# Blank_Ext_Board.net
KiCad netlist of a schematic drawn in EAGLE
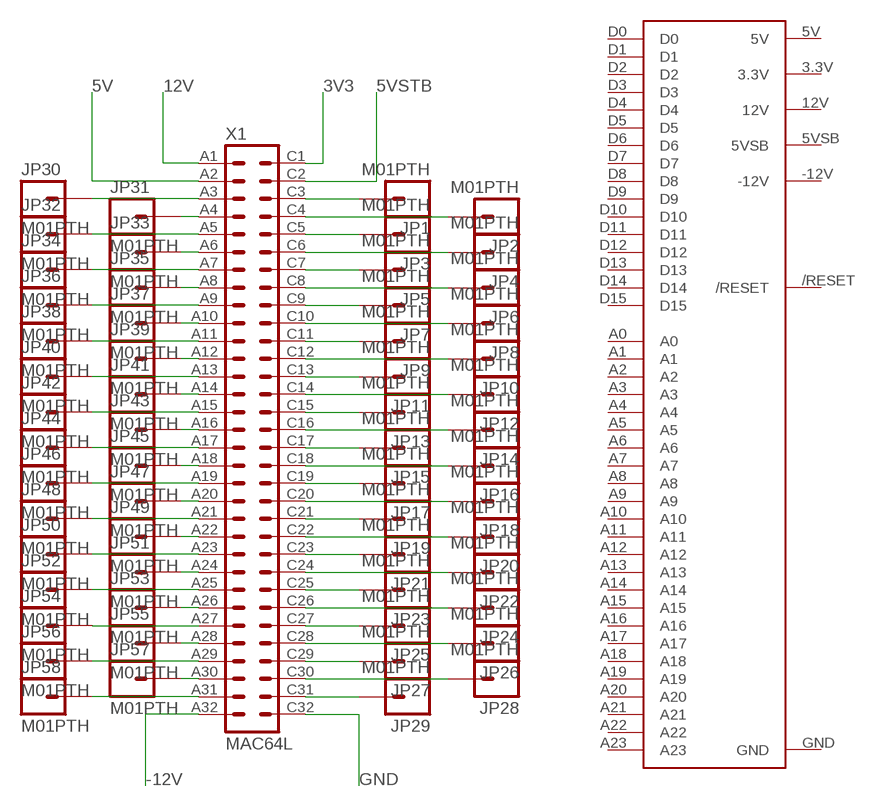
[diagram p0: schematic, sheet 1]

(export (version "E")
  (design (tool "Eeschema 10.0.6"))
  (components
    (comp (ref "JP1")
      (value "M01PTH")
      (footprint "eagle-import:1X01")
      (libsource (lib "eagle-import") (part "M01PTH"))
    )
    (comp (ref "JP2")
      (value "M01PTH")
      (footprint "eagle-import:1X01")
      (libsource (lib "eagle-import") (part "M01PTH"))
    )
    (comp (ref "JP3")
      (value "M01PTH")
      (footprint "eagle-import:1X01")
      (libsource (lib "eagle-import") (part "M01PTH"))
    )
    (comp (ref "JP4")
      (value "M01PTH")
      (footprint "eagle-import:1X01")
      (libsource (lib "eagle-import") (part "M01PTH"))
    )
    (comp (ref "JP5")
      (value "M01PTH")
      (footprint "eagle-import:1X01")
      (libsource (lib "eagle-import") (part "M01PTH"))
    )
    (comp (ref "JP6")
      (value "M01PTH")
      (footprint "eagle-import:1X01")
      (libsource (lib "eagle-import") (part "M01PTH"))
    )
    (comp (ref "JP7")
      (value "M01PTH")
      (footprint "eagle-import:1X01")
      (libsource (lib "eagle-import") (part "M01PTH"))
    )
    (comp (ref "JP8")
      (value "M01PTH")
      (footprint "eagle-import:1X01")
      (libsource (lib "eagle-import") (part "M01PTH"))
    )
    (comp (ref "JP9")
      (value "M01PTH")
      (footprint "eagle-import:1X01")
      (libsource (lib "eagle-import") (part "M01PTH"))
    )
    (comp (ref "JP10")
      (value "M01PTH")
      (footprint "eagle-import:1X01")
      (libsource (lib "eagle-import") (part "M01PTH"))
    )
    (comp (ref "JP11")
      (value "M01PTH")
      (footprint "eagle-import:1X01")
      (libsource (lib "eagle-import") (part "M01PTH"))
    )
    (comp (ref "JP12")
      (value "M01PTH")
      (footprint "eagle-import:1X01")
      (libsource (lib "eagle-import") (part "M01PTH"))
    )
    (comp (ref "JP13")
      (value "M01PTH")
      (footprint "eagle-import:1X01")
      (libsource (lib "eagle-import") (part "M01PTH"))
    )
    (comp (ref "JP14")
      (value "M01PTH")
      (footprint "eagle-import:1X01")
      (libsource (lib "eagle-import") (part "M01PTH"))
    )
    (comp (ref "JP15")
      (value "M01PTH")
      (footprint "eagle-import:1X01")
      (libsource (lib "eagle-import") (part "M01PTH"))
    )
    (comp (ref "JP16")
      (value "M01PTH")
      (footprint "eagle-import:1X01")
      (libsource (lib "eagle-import") (part "M01PTH"))
    )
    (comp (ref "JP17")
      (value "M01PTH")
      (footprint "eagle-import:1X01")
      (libsource (lib "eagle-import") (part "M01PTH"))
    )
    (comp (ref "JP18")
      (value "M01PTH")
      (footprint "eagle-import:1X01")
      (libsource (lib "eagle-import") (part "M01PTH"))
    )
    (comp (ref "JP19")
      (value "M01PTH")
      (footprint "eagle-import:1X01")
      (libsource (lib "eagle-import") (part "M01PTH"))
    )
    (comp (ref "JP20")
      (value "M01PTH")
      (footprint "eagle-import:1X01")
      (libsource (lib "eagle-import") (part "M01PTH"))
    )
    (comp (ref "JP21")
      (value "M01PTH")
      (footprint "eagle-import:1X01")
      (libsource (lib "eagle-import") (part "M01PTH"))
    )
    (comp (ref "JP22")
      (value "M01PTH")
      (footprint "eagle-import:1X01")
      (libsource (lib "eagle-import") (part "M01PTH"))
    )
    (comp (ref "JP23")
      (value "M01PTH")
      (footprint "eagle-import:1X01")
      (libsource (lib "eagle-import") (part "M01PTH"))
    )
    (comp (ref "JP24")
      (value "M01PTH")
      (footprint "eagle-import:1X01")
      (libsource (lib "eagle-import") (part "M01PTH"))
    )
    (comp (ref "JP25")
      (value "M01PTH")
      (footprint "eagle-import:1X01")
      (libsource (lib "eagle-import") (part "M01PTH"))
    )
    (comp (ref "JP26")
      (value "M01PTH")
      (footprint "eagle-import:1X01")
      (libsource (lib "eagle-import") (part "M01PTH"))
    )
    (comp (ref "JP27")
      (value "M01PTH")
      (footprint "eagle-import:1X01")
      (libsource (lib "eagle-import") (part "M01PTH"))
    )
    (comp (ref "JP28")
      (value "M01PTH")
      (footprint "eagle-import:1X01")
      (libsource (lib "eagle-import") (part "M01PTH"))
    )
    (comp (ref "JP29")
      (value "M01PTH")
      (footprint "eagle-import:1X01")
      (libsource (lib "eagle-import") (part "M01PTH"))
    )
    (comp (ref "JP30")
      (value "M01PTH")
      (footprint "eagle-import:1X01")
      (libsource (lib "eagle-import") (part "M01PTH"))
    )
    (comp (ref "JP31")
      (value "M01PTH")
      (footprint "eagle-import:1X01")
      (libsource (lib "eagle-import") (part "M01PTH"))
    )
    (comp (ref "JP32")
      (value "M01PTH")
      (footprint "eagle-import:1X01")
      (libsource (lib "eagle-import") (part "M01PTH"))
    )
    (comp (ref "JP33")
      (value "M01PTH")
      (footprint "eagle-import:1X01")
      (libsource (lib "eagle-import") (part "M01PTH"))
    )
    (comp (ref "JP34")
      (value "M01PTH")
      (footprint "eagle-import:1X01")
      (libsource (lib "eagle-import") (part "M01PTH"))
    )
    (comp (ref "JP35")
      (value "M01PTH")
      (footprint "eagle-import:1X01")
      (libsource (lib "eagle-import") (part "M01PTH"))
    )
    (comp (ref "JP36")
      (value "M01PTH")
      (footprint "eagle-import:1X01")
      (libsource (lib "eagle-import") (part "M01PTH"))
    )
    (comp (ref "JP37")
      (value "M01PTH")
      (footprint "eagle-import:1X01")
      (libsource (lib "eagle-import") (part "M01PTH"))
    )
    (comp (ref "JP38")
      (value "M01PTH")
      (footprint "eagle-import:1X01")
      (libsource (lib "eagle-import") (part "M01PTH"))
    )
    (comp (ref "JP39")
      (value "M01PTH")
      (footprint "eagle-import:1X01")
      (libsource (lib "eagle-import") (part "M01PTH"))
    )
    (comp (ref "JP40")
      (value "M01PTH")
      (footprint "eagle-import:1X01")
      (libsource (lib "eagle-import") (part "M01PTH"))
    )
    (comp (ref "JP41")
      (value "M01PTH")
      (footprint "eagle-import:1X01")
      (libsource (lib "eagle-import") (part "M01PTH"))
    )
    (comp (ref "JP42")
      (value "M01PTH")
      (footprint "eagle-import:1X01")
      (libsource (lib "eagle-import") (part "M01PTH"))
    )
    (comp (ref "JP43")
      (value "M01PTH")
      (footprint "eagle-import:1X01")
      (libsource (lib "eagle-import") (part "M01PTH"))
    )
    (comp (ref "JP44")
      (value "M01PTH")
      (footprint "eagle-import:1X01")
      (libsource (lib "eagle-import") (part "M01PTH"))
    )
    (comp (ref "JP45")
      (value "M01PTH")
      (footprint "eagle-import:1X01")
      (libsource (lib "eagle-import") (part "M01PTH"))
    )
    (comp (ref "JP46")
      (value "M01PTH")
      (footprint "eagle-import:1X01")
      (libsource (lib "eagle-import") (part "M01PTH"))
    )
    (comp (ref "JP47")
      (value "M01PTH")
      (footprint "eagle-import:1X01")
      (libsource (lib "eagle-import") (part "M01PTH"))
    )
    (comp (ref "JP48")
      (value "M01PTH")
      (footprint "eagle-import:1X01")
      (libsource (lib "eagle-import") (part "M01PTH"))
    )
    (comp (ref "JP49")
      (value "M01PTH")
      (footprint "eagle-import:1X01")
      (libsource (lib "eagle-import") (part "M01PTH"))
    )
    (comp (ref "JP50")
      (value "M01PTH")
      (footprint "eagle-import:1X01")
      (libsource (lib "eagle-import") (part "M01PTH"))
    )
    (comp (ref "JP51")
      (value "M01PTH")
      (footprint "eagle-import:1X01")
      (libsource (lib "eagle-import") (part "M01PTH"))
    )
    (comp (ref "JP52")
      (value "M01PTH")
      (footprint "eagle-import:1X01")
      (libsource (lib "eagle-import") (part "M01PTH"))
    )
    (comp (ref "JP53")
      (value "M01PTH")
      (footprint "eagle-import:1X01")
      (libsource (lib "eagle-import") (part "M01PTH"))
    )
    (comp (ref "JP54")
      (value "M01PTH")
      (footprint "eagle-import:1X01")
      (libsource (lib "eagle-import") (part "M01PTH"))
    )
    (comp (ref "JP55")
      (value "M01PTH")
      (footprint "eagle-import:1X01")
      (libsource (lib "eagle-import") (part "M01PTH"))
    )
    (comp (ref "JP56")
      (value "M01PTH")
      (footprint "eagle-import:1X01")
      (libsource (lib "eagle-import") (part "M01PTH"))
    )
    (comp (ref "JP57")
      (value "M01PTH")
      (footprint "eagle-import:1X01")
      (libsource (lib "eagle-import") (part "M01PTH"))
    )
    (comp (ref "JP58")
      (value "M01PTH")
      (footprint "eagle-import:1X01")
      (libsource (lib "eagle-import") (part "M01PTH"))
    )
    (comp (ref "U$3")
      (value "BACKPLANEBOARD")
      (footprint "eagle-import:BACKPLANEBOARD")
      (libsource (lib "eagle-import") (part "BACKPLANEBOARD"))
    )
    (comp (ref "X1")
      (value "MAC64L")
      (footprint "eagle-import:MAC64L")
      (libsource (lib "eagle-import") (part "MAC64L"))
    )
  )
  (nets
    (net (code "1") (name "/-12V") (class "Default")
      (node (ref "X1") (pin "A32") (pinfunction "A32_A32") (pintype "passive"))
    )
    (net (code "2") (name "/3V3") (class "Default")
      (node (ref "X1") (pin "C1") (pinfunction "C1_C1") (pintype "passive"))
    )
    (net (code "3") (name "/5V") (class "Default")
      (node (ref "X1") (pin "A2") (pinfunction "A2_A2") (pintype "passive"))
    )
    (net (code "4") (name "/5VSTB") (class "Default")
      (node (ref "X1") (pin "C2") (pinfunction "C2_C2") (pintype "passive"))
    )
    (net (code "5") (name "/12V") (class "Default")
      (node (ref "X1") (pin "A1") (pinfunction "A1_A1") (pintype "passive"))
    )
    (net (code "6") (name "/GND") (class "Default")
      (node (ref "X1") (pin "C32") (pinfunction "C32_C32") (pintype "passive"))
    )
    (net (code "7") (name "Net-(JP1-Pad1)") (class "Default")
      (node (ref "JP1") (pin "1") (pinfunction "1_1") (pintype "passive"))
      (node (ref "X1") (pin "C3") (pinfunction "C3_C3") (pintype "passive"))
    )
    (net (code "8") (name "Net-(JP2-Pad1)") (class "Default")
      (node (ref "JP2") (pin "1") (pinfunction "1_1") (pintype "passive"))
      (node (ref "X1") (pin "C4") (pinfunction "C4_C4") (pintype "passive"))
    )
    (net (code "9") (name "Net-(JP3-Pad1)") (class "Default")
      (node (ref "JP3") (pin "1") (pinfunction "1_1") (pintype "passive"))
      (node (ref "X1") (pin "C5") (pinfunction "C5_C5") (pintype "passive"))
    )
    (net (code "10") (name "Net-(JP4-Pad1)") (class "Default")
      (node (ref "JP4") (pin "1") (pinfunction "1_1") (pintype "passive"))
      (node (ref "X1") (pin "C6") (pinfunction "C6_C6") (pintype "passive"))
    )
    (net (code "11") (name "Net-(JP5-Pad1)") (class "Default")
      (node (ref "JP5") (pin "1") (pinfunction "1_1") (pintype "passive"))
      (node (ref "X1") (pin "C7") (pinfunction "C7_C7") (pintype "passive"))
    )
    (net (code "12") (name "Net-(JP6-Pad1)") (class "Default")
      (node (ref "JP6") (pin "1") (pinfunction "1_1") (pintype "passive"))
      (node (ref "X1") (pin "C8") (pinfunction "C8_C8") (pintype "passive"))
    )
    (net (code "13") (name "Net-(JP7-Pad1)") (class "Default")
      (node (ref "JP7") (pin "1") (pinfunction "1_1") (pintype "passive"))
      (node (ref "X1") (pin "C9") (pinfunction "C9_C9") (pintype "passive"))
    )
    (net (code "14") (name "Net-(JP8-Pad1)") (class "Default")
      (node (ref "JP8") (pin "1") (pinfunction "1_1") (pintype "passive"))
      (node (ref "X1") (pin "C10") (pinfunction "C10_C10") (pintype "passive"))
    )
    (net (code "15") (name "Net-(JP9-Pad1)") (class "Default")
      (node (ref "JP9") (pin "1") (pinfunction "1_1") (pintype "passive"))
      (node (ref "X1") (pin "C11") (pinfunction "C11_C11") (pintype "passive"))
    )
    (net (code "16") (name "Net-(JP10-Pad1)") (class "Default")
      (node (ref "JP10") (pin "1") (pinfunction "1_1") (pintype "passive"))
      (node (ref "X1") (pin "C12") (pinfunction "C12_C12") (pintype "passive"))
    )
    (net (code "17") (name "Net-(JP11-Pad1)") (class "Default")
      (node (ref "JP11") (pin "1") (pinfunction "1_1") (pintype "passive"))
      (node (ref "X1") (pin "C13") (pinfunction "C13_C13") (pintype "passive"))
    )
    (net (code "18") (name "Net-(JP12-Pad1)") (class "Default")
      (node (ref "JP12") (pin "1") (pinfunction "1_1") (pintype "passive"))
      (node (ref "X1") (pin "C14") (pinfunction "C14_C14") (pintype "passive"))
    )
    (net (code "19") (name "Net-(JP13-Pad1)") (class "Default")
      (node (ref "JP13") (pin "1") (pinfunction "1_1") (pintype "passive"))
      (node (ref "X1") (pin "C15") (pinfunction "C15_C15") (pintype "passive"))
    )
    (net (code "20") (name "Net-(JP14-Pad1)") (class "Default")
      (node (ref "JP14") (pin "1") (pinfunction "1_1") (pintype "passive"))
      (node (ref "X1") (pin "C16") (pinfunction "C16_C16") (pintype "passive"))
    )
    (net (code "21") (name "Net-(JP15-Pad1)") (class "Default")
      (node (ref "JP15") (pin "1") (pinfunction "1_1") (pintype "passive"))
      (node (ref "X1") (pin "C17") (pinfunction "C17_C17") (pintype "passive"))
    )
    (net (code "22") (name "Net-(JP16-Pad1)") (class "Default")
      (node (ref "JP16") (pin "1") (pinfunction "1_1") (pintype "passive"))
      (node (ref "X1") (pin "C18") (pinfunction "C18_C18") (pintype "passive"))
    )
    (net (code "23") (name "Net-(JP17-Pad1)") (class "Default")
      (node (ref "JP17") (pin "1") (pinfunction "1_1") (pintype "passive"))
      (node (ref "X1") (pin "C19") (pinfunction "C19_C19") (pintype "passive"))
    )
    (net (code "24") (name "Net-(JP18-Pad1)") (class "Default")
      (node (ref "JP18") (pin "1") (pinfunction "1_1") (pintype "passive"))
      (node (ref "X1") (pin "C20") (pinfunction "C20_C20") (pintype "passive"))
    )
    (net (code "25") (name "Net-(JP19-Pad1)") (class "Default")
      (node (ref "JP19") (pin "1") (pinfunction "1_1") (pintype "passive"))
      (node (ref "X1") (pin "C21") (pinfunction "C21_C21") (pintype "passive"))
    )
    (net (code "26") (name "Net-(JP20-Pad1)") (class "Default")
      (node (ref "JP20") (pin "1") (pinfunction "1_1") (pintype "passive"))
      (node (ref "X1") (pin "C22") (pinfunction "C22_C22") (pintype "passive"))
    )
    (net (code "27") (name "Net-(JP21-Pad1)") (class "Default")
      (node (ref "JP21") (pin "1") (pinfunction "1_1") (pintype "passive"))
      (node (ref "X1") (pin "C23") (pinfunction "C23_C23") (pintype "passive"))
    )
    (net (code "28") (name "Net-(JP22-Pad1)") (class "Default")
      (node (ref "JP22") (pin "1") (pinfunction "1_1") (pintype "passive"))
      (node (ref "X1") (pin "C24") (pinfunction "C24_C24") (pintype "passive"))
    )
    (net (code "29") (name "Net-(JP23-Pad1)") (class "Default")
      (node (ref "JP23") (pin "1") (pinfunction "1_1") (pintype "passive"))
      (node (ref "X1") (pin "C25") (pinfunction "C25_C25") (pintype "passive"))
    )
    (net (code "30") (name "Net-(JP24-Pad1)") (class "Default")
      (node (ref "JP24") (pin "1") (pinfunction "1_1") (pintype "passive"))
      (node (ref "X1") (pin "C26") (pinfunction "C26_C26") (pintype "passive"))
    )
    (net (code "31") (name "Net-(JP25-Pad1)") (class "Default")
      (node (ref "JP25") (pin "1") (pinfunction "1_1") (pintype "passive"))
      (node (ref "X1") (pin "C27") (pinfunction "C27_C27") (pintype "passive"))
    )
    (net (code "32") (name "Net-(JP26-Pad1)") (class "Default")
      (node (ref "JP26") (pin "1") (pinfunction "1_1") (pintype "passive"))
      (node (ref "X1") (pin "C28") (pinfunction "C28_C28") (pintype "passive"))
    )
    (net (code "33") (name "Net-(JP27-Pad1)") (class "Default")
      (node (ref "JP27") (pin "1") (pinfunction "1_1") (pintype "passive"))
      (node (ref "X1") (pin "C29") (pinfunction "C29_C29") (pintype "passive"))
    )
    (net (code "34") (name "Net-(JP28-Pad1)") (class "Default")
      (node (ref "JP28") (pin "1") (pinfunction "1_1") (pintype "passive"))
      (node (ref "X1") (pin "C30") (pinfunction "C30_C30") (pintype "passive"))
    )
    (net (code "35") (name "Net-(JP29-Pad1)") (class "Default")
      (node (ref "JP29") (pin "1") (pinfunction "1_1") (pintype "passive"))
      (node (ref "X1") (pin "C31") (pinfunction "C31_C31") (pintype "passive"))
    )
    (net (code "36") (name "Net-(JP30-Pad1)") (class "Default")
      (node (ref "JP30") (pin "1") (pinfunction "1_1") (pintype "passive"))
      (node (ref "X1") (pin "A3") (pinfunction "A3_A3") (pintype "passive"))
    )
    (net (code "37") (name "Net-(JP31-Pad1)") (class "Default")
      (node (ref "JP31") (pin "1") (pinfunction "1_1") (pintype "passive"))
      (node (ref "X1") (pin "A4") (pinfunction "A4_A4") (pintype "passive"))
    )
    (net (code "38") (name "Net-(JP32-Pad1)") (class "Default")
      (node (ref "JP32") (pin "1") (pinfunction "1_1") (pintype "passive"))
      (node (ref "X1") (pin "A5") (pinfunction "A5_A5") (pintype "passive"))
    )
    (net (code "39") (name "Net-(JP33-Pad1)") (class "Default")
      (node (ref "JP33") (pin "1") (pinfunction "1_1") (pintype "passive"))
      (node (ref "X1") (pin "A6") (pinfunction "A6_A6") (pintype "passive"))
    )
    (net (code "40") (name "Net-(JP34-Pad1)") (class "Default")
      (node (ref "JP34") (pin "1") (pinfunction "1_1") (pintype "passive"))
      (node (ref "X1") (pin "A7") (pinfunction "A7_A7") (pintype "passive"))
    )
    (net (code "41") (name "Net-(JP35-Pad1)") (class "Default")
      (node (ref "JP35") (pin "1") (pinfunction "1_1") (pintype "passive"))
      (node (ref "X1") (pin "A8") (pinfunction "A8_A8") (pintype "passive"))
    )
    (net (code "42") (name "Net-(JP36-Pad1)") (class "Default")
      (node (ref "JP36") (pin "1") (pinfunction "1_1") (pintype "passive"))
      (node (ref "X1") (pin "A9") (pinfunction "A9_A9") (pintype "passive"))
    )
    (net (code "43") (name "Net-(JP37-Pad1)") (class "Default")
      (node (ref "JP37") (pin "1") (pinfunction "1_1") (pintype "passive"))
      (node (ref "X1") (pin "A10") (pinfunction "A10_A10") (pintype "passive"))
    )
    (net (code "44") (name "Net-(JP38-Pad1)") (class "Default")
      (node (ref "JP38") (pin "1") (pinfunction "1_1") (pintype "passive"))
      (node (ref "X1") (pin "A11") (pinfunction "A11_A11") (pintype "passive"))
    )
    (net (code "45") (name "Net-(JP39-Pad1)") (class "Default")
      (node (ref "JP39") (pin "1") (pinfunction "1_1") (pintype "passive"))
      (node (ref "X1") (pin "A12") (pinfunction "A12_A12") (pintype "passive"))
    )
    (net (code "46") (name "Net-(JP40-Pad1)") (class "Default")
      (node (ref "JP40") (pin "1") (pinfunction "1_1") (pintype "passive"))
      (node (ref "X1") (pin "A13") (pinfunction "A13_A13") (pintype "passive"))
    )
    (net (code "47") (name "Net-(JP41-Pad1)") (class "Default")
      (node (ref "JP41") (pin "1") (pinfunction "1_1") (pintype "passive"))
      (node (ref "X1") (pin "A14") (pinfunction "A14_A14") (pintype "passive"))
    )
    (net (code "48") (name "Net-(JP42-Pad1)") (class "Default")
      (node (ref "JP42") (pin "1") (pinfunction "1_1") (pintype "passive"))
      (node (ref "X1") (pin "A15") (pinfunction "A15_A15") (pintype "passive"))
    )
    (net (code "49") (name "Net-(JP43-Pad1)") (class "Default")
      (node (ref "JP43") (pin "1") (pinfunction "1_1") (pintype "passive"))
      (node (ref "X1") (pin "A16") (pinfunction "A16_A16") (pintype "passive"))
    )
    (net (code "50") (name "Net-(JP44-Pad1)") (class "Default")
      (node (ref "JP44") (pin "1") (pinfunction "1_1") (pintype "passive"))
      (node (ref "X1") (pin "A17") (pinfunction "A17_A17") (pintype "passive"))
    )
    (net (code "51") (name "Net-(JP45-Pad1)") (class "Default")
      (node (ref "JP45") (pin "1") (pinfunction "1_1") (pintype "passive"))
      (node (ref "X1") (pin "A18") (pinfunction "A18_A18") (pintype "passive"))
    )
    (net (code "52") (name "Net-(JP46-Pad1)") (class "Default")
      (node (ref "JP46") (pin "1") (pinfunction "1_1") (pintype "passive"))
      (node (ref "X1") (pin "A19") (pinfunction "A19_A19") (pintype "passive"))
    )
    (net (code "53") (name "Net-(JP47-Pad1)") (class "Default")
      (node (ref "JP47") (pin "1") (pinfunction "1_1") (pintype "passive"))
      (node (ref "X1") (pin "A20") (pinfunction "A20_A20") (pintype "passive"))
    )
    (net (code "54") (name "Net-(JP48-Pad1)") (class "Default")
      (node (ref "JP48") (pin "1") (pinfunction "1_1") (pintype "passive"))
      (node (ref "X1") (pin "A21") (pinfunction "A21_A21") (pintype "passive"))
    )
    (net (code "55") (name "Net-(JP49-Pad1)") (class "Default")
      (node (ref "JP49") (pin "1") (pinfunction "1_1") (pintype "passive"))
      (node (ref "X1") (pin "A22") (pinfunction "A22_A22") (pintype "passive"))
    )
    (net (code "56") (name "Net-(JP50-Pad1)") (class "Default")
      (node (ref "JP50") (pin "1") (pinfunction "1_1") (pintype "passive"))
      (node (ref "X1") (pin "A23") (pinfunction "A23_A23") (pintype "passive"))
    )
    (net (code "57") (name "Net-(JP51-Pad1)") (class "Default")
      (node (ref "JP51") (pin "1") (pinfunction "1_1") (pintype "passive"))
      (node (ref "X1") (pin "A24") (pinfunction "A24_A24") (pintype "passive"))
    )
    (net (code "58") (name "Net-(JP52-Pad1)") (class "Default")
      (node (ref "JP52") (pin "1") (pinfunction "1_1") (pintype "passive"))
      (node (ref "X1") (pin "A25") (pinfunction "A25_A25") (pintype "passive"))
    )
    (net (code "59") (name "Net-(JP53-Pad1)") (class "Default")
      (node (ref "JP53") (pin "1") (pinfunction "1_1") (pintype "passive"))
      (node (ref "X1") (pin "A26") (pinfunction "A26_A26") (pintype "passive"))
    )
    (net (code "60") (name "Net-(JP54-Pad1)") (class "Default")
      (node (ref "JP54") (pin "1") (pinfunction "1_1") (pintype "passive"))
      (node (ref "X1") (pin "A27") (pinfunction "A27_A27") (pintype "passive"))
    )
    (net (code "61") (name "Net-(JP55-Pad1)") (class "Default")
      (node (ref "JP55") (pin "1") (pinfunction "1_1") (pintype "passive"))
      (node (ref "X1") (pin "A28") (pinfunction "A28_A28") (pintype "passive"))
    )
    (net (code "62") (name "Net-(JP56-Pad1)") (class "Default")
      (node (ref "JP56") (pin "1") (pinfunction "1_1") (pintype "passive"))
      (node (ref "X1") (pin "A29") (pinfunction "A29_A29") (pintype "passive"))
    )
    (net (code "63") (name "Net-(JP57-Pad1)") (class "Default")
      (node (ref "JP57") (pin "1") (pinfunction "1_1") (pintype "passive"))
      (node (ref "X1") (pin "A30") (pinfunction "A30_A30") (pintype "passive"))
    )
    (net (code "64") (name "Net-(JP58-Pad1)") (class "Default")
      (node (ref "JP58") (pin "1") (pinfunction "1_1") (pintype "passive"))
      (node (ref "X1") (pin "A31") (pinfunction "A31_A31") (pintype "passive"))
    )
    (net (code "65") (name "unconnected-(U$3-Pad-12V)") (class "Default")
      (node (ref "U$3") (pin "-12V") (pinfunction "-12V_-12V") (pintype "bidirectional"))
    )
    (net (code "66") (name "unconnected-(U$3-Pad3.3V)") (class "Default")
      (node (ref "U$3") (pin "3.3V") (pinfunction "3.3V_3.3V") (pintype "bidirectional"))
    )
    (net (code "67") (name "unconnected-(U$3-Pad5V)") (class "Default")
      (node (ref "U$3") (pin "5V") (pinfunction "5V_5V") (pintype "bidirectional"))
    )
    (net (code "68") (name "unconnected-(U$3-Pad5VSB)") (class "Default")
      (node (ref "U$3") (pin "5VSB") (pinfunction "5VSB_5VSB") (pintype "bidirectional"))
    )
    (net (code "69") (name "unconnected-(U$3-Pad12V)") (class "Default")
      (node (ref "U$3") (pin "12V") (pinfunction "12V_12V") (pintype "bidirectional"))
    )
    (net (code "70") (name "unconnected-(U$3-PadA0)") (class "Default")
      (node (ref "U$3") (pin "A0") (pinfunction "A0_A0") (pintype "bidirectional"))
    )
    (net (code "71") (name "unconnected-(U$3-PadA1)") (class "Default")
      (node (ref "U$3") (pin "A1") (pinfunction "A1_A1") (pintype "bidirectional"))
    )
    (net (code "72") (name "unconnected-(U$3-PadA2)") (class "Default")
      (node (ref "U$3") (pin "A2") (pinfunction "A2_A2") (pintype "bidirectional"))
    )
    (net (code "73") (name "unconnected-(U$3-PadA3)") (class "Default")
      (node (ref "U$3") (pin "A3") (pinfunction "A3_A3") (pintype "bidirectional"))
    )
    (net (code "74") (name "unconnected-(U$3-PadA4)") (class "Default")
      (node (ref "U$3") (pin "A4") (pinfunction "A4_A4") (pintype "bidirectional"))
    )
    (net (code "75") (name "unconnected-(U$3-PadA5)") (class "Default")
      (node (ref "U$3") (pin "A5") (pinfunction "A5_A5") (pintype "bidirectional"))
    )
    (net (code "76") (name "unconnected-(U$3-PadA6)") (class "Default")
      (node (ref "U$3") (pin "A6") (pinfunction "A6_A6") (pintype "bidirectional"))
    )
    (net (code "77") (name "unconnected-(U$3-PadA7)") (class "Default")
      (node (ref "U$3") (pin "A7") (pinfunction "A7_A7") (pintype "bidirectional"))
    )
    (net (code "78") (name "unconnected-(U$3-PadA8)") (class "Default")
      (node (ref "U$3") (pin "A8") (pinfunction "A8_A8") (pintype "bidirectional"))
    )
    (net (code "79") (name "unconnected-(U$3-PadA9)") (class "Default")
      (node (ref "U$3") (pin "A9") (pinfunction "A9_A9") (pintype "bidirectional"))
    )
    (net (code "80") (name "unconnected-(U$3-PadA10)") (class "Default")
      (node (ref "U$3") (pin "A10") (pinfunction "A10_A10") (pintype "bidirectional"))
    )
    (net (code "81") (name "unconnected-(U$3-PadA11)") (class "Default")
      (node (ref "U$3") (pin "A11") (pinfunction "A11_A11") (pintype "bidirectional"))
    )
    (net (code "82") (name "unconnected-(U$3-PadA12)") (class "Default")
      (node (ref "U$3") (pin "A12") (pinfunction "A12_A12") (pintype "bidirectional"))
    )
    (net (code "83") (name "unconnected-(U$3-PadA13)") (class "Default")
      (node (ref "U$3") (pin "A13") (pinfunction "A13_A13") (pintype "bidirectional"))
    )
    (net (code "84") (name "unconnected-(U$3-PadA14)") (class "Default")
      (node (ref "U$3") (pin "A14") (pinfunction "A14_A14") (pintype "bidirectional"))
    )
    (net (code "85") (name "unconnected-(U$3-PadA15)") (class "Default")
      (node (ref "U$3") (pin "A15") (pinfunction "A15_A15") (pintype "bidirectional"))
    )
    (net (code "86") (name "unconnected-(U$3-PadA16)") (class "Default")
      (node (ref "U$3") (pin "A16") (pinfunction "A16_A16") (pintype "bidirectional"))
    )
    (net (code "87") (name "unconnected-(U$3-PadA17)") (class "Default")
      (node (ref "U$3") (pin "A17") (pinfunction "A17_A17") (pintype "bidirectional"))
    )
    (net (code "88") (name "unconnected-(U$3-PadA18)") (class "Default")
      (node (ref "U$3") (pin "A18") (pinfunction "A18_A18") (pintype "bidirectional"))
    )
    (net (code "89") (name "unconnected-(U$3-PadA19)") (class "Default")
      (node (ref "U$3") (pin "A19") (pinfunction "A19_A19") (pintype "bidirectional"))
    )
    (net (code "90") (name "unconnected-(U$3-PadA20)") (class "Default")
      (node (ref "U$3") (pin "A20") (pinfunction "A20_A20") (pintype "bidirectional"))
    )
    (net (code "91") (name "unconnected-(U$3-PadA21)") (class "Default")
      (node (ref "U$3") (pin "A21") (pinfunction "A21_A21") (pintype "bidirectional"))
    )
    (net (code "92") (name "unconnected-(U$3-PadA22)") (class "Default")
      (node (ref "U$3") (pin "A22") (pinfunction "A22_A22") (pintype "bidirectional"))
    )
    (net (code "93") (name "unconnected-(U$3-PadA23)") (class "Default")
      (node (ref "U$3") (pin "A23") (pinfunction "A23_A23") (pintype "bidirectional"))
    )
    (net (code "94") (name "unconnected-(U$3-PadD0)") (class "Default")
      (node (ref "U$3") (pin "D0") (pinfunction "D0_D0") (pintype "bidirectional"))
    )
    (net (code "95") (name "unconnected-(U$3-PadD1)") (class "Default")
      (node (ref "U$3") (pin "D1") (pinfunction "D1_D1") (pintype "bidirectional"))
    )
    (net (code "96") (name "unconnected-(U$3-PadD2)") (class "Default")
      (node (ref "U$3") (pin "D2") (pinfunction "D2_D2") (pintype "bidirectional"))
    )
    (net (code "97") (name "unconnected-(U$3-PadD3)") (class "Default")
      (node (ref "U$3") (pin "D3") (pinfunction "D3_D3") (pintype "bidirectional"))
    )
    (net (code "98") (name "unconnected-(U$3-PadD4)") (class "Default")
      (node (ref "U$3") (pin "D4") (pinfunction "D4_D4") (pintype "bidirectional"))
    )
    (net (code "99") (name "unconnected-(U$3-PadD5)") (class "Default")
      (node (ref "U$3") (pin "D5") (pinfunction "D5_D5") (pintype "bidirectional"))
    )
    (net (code "100") (name "unconnected-(U$3-PadD6)") (class "Default")
      (node (ref "U$3") (pin "D6") (pinfunction "D6_D6") (pintype "bidirectional"))
    )
    (net (code "101") (name "unconnected-(U$3-PadD7)") (class "Default")
      (node (ref "U$3") (pin "D7") (pinfunction "D7_D7") (pintype "bidirectional"))
    )
    (net (code "102") (name "unconnected-(U$3-PadD8)") (class "Default")
      (node (ref "U$3") (pin "D8") (pinfunction "D8_D8") (pintype "bidirectional"))
    )
    (net (code "103") (name "unconnected-(U$3-PadD9)") (class "Default")
      (node (ref "U$3") (pin "D9") (pinfunction "D9_D9") (pintype "bidirectional"))
    )
    (net (code "104") (name "unconnected-(U$3-PadD10)") (class "Default")
      (node (ref "U$3") (pin "D10") (pinfunction "D10_D10") (pintype "bidirectional"))
    )
    (net (code "105") (name "unconnected-(U$3-PadD11)") (class "Default")
      (node (ref "U$3") (pin "D11") (pinfunction "D11_D11") (pintype "bidirectional"))
    )
    (net (code "106") (name "unconnected-(U$3-PadD12)") (class "Default")
      (node (ref "U$3") (pin "D12") (pinfunction "D12_D12") (pintype "bidirectional"))
    )
    (net (code "107") (name "unconnected-(U$3-PadD13)") (class "Default")
      (node (ref "U$3") (pin "D13") (pinfunction "D13_D13") (pintype "bidirectional"))
    )
    (net (code "108") (name "unconnected-(U$3-PadD14)") (class "Default")
      (node (ref "U$3") (pin "D14") (pinfunction "D14_D14") (pintype "bidirectional"))
    )
    (net (code "109") (name "unconnected-(U$3-PadD15)") (class "Default")
      (node (ref "U$3") (pin "D15") (pinfunction "D15_D15") (pintype "bidirectional"))
    )
    (net (code "110") (name "unconnected-(U$3-PadGND)") (class "Default")
      (node (ref "U$3") (pin "GND") (pinfunction "GND_GND") (pintype "bidirectional"))
    )
    (net (code "111") (name "unconnected-(U$3-Pad{slash}RESET)") (class "Default")
      (node (ref "U$3") (pin "/RESET") (pinfunction "/RESET_/RESET") (pintype "bidirectional"))
    )
  )
)
